# power.net
KiCad netlist of a schematic drawn in Altium Designer
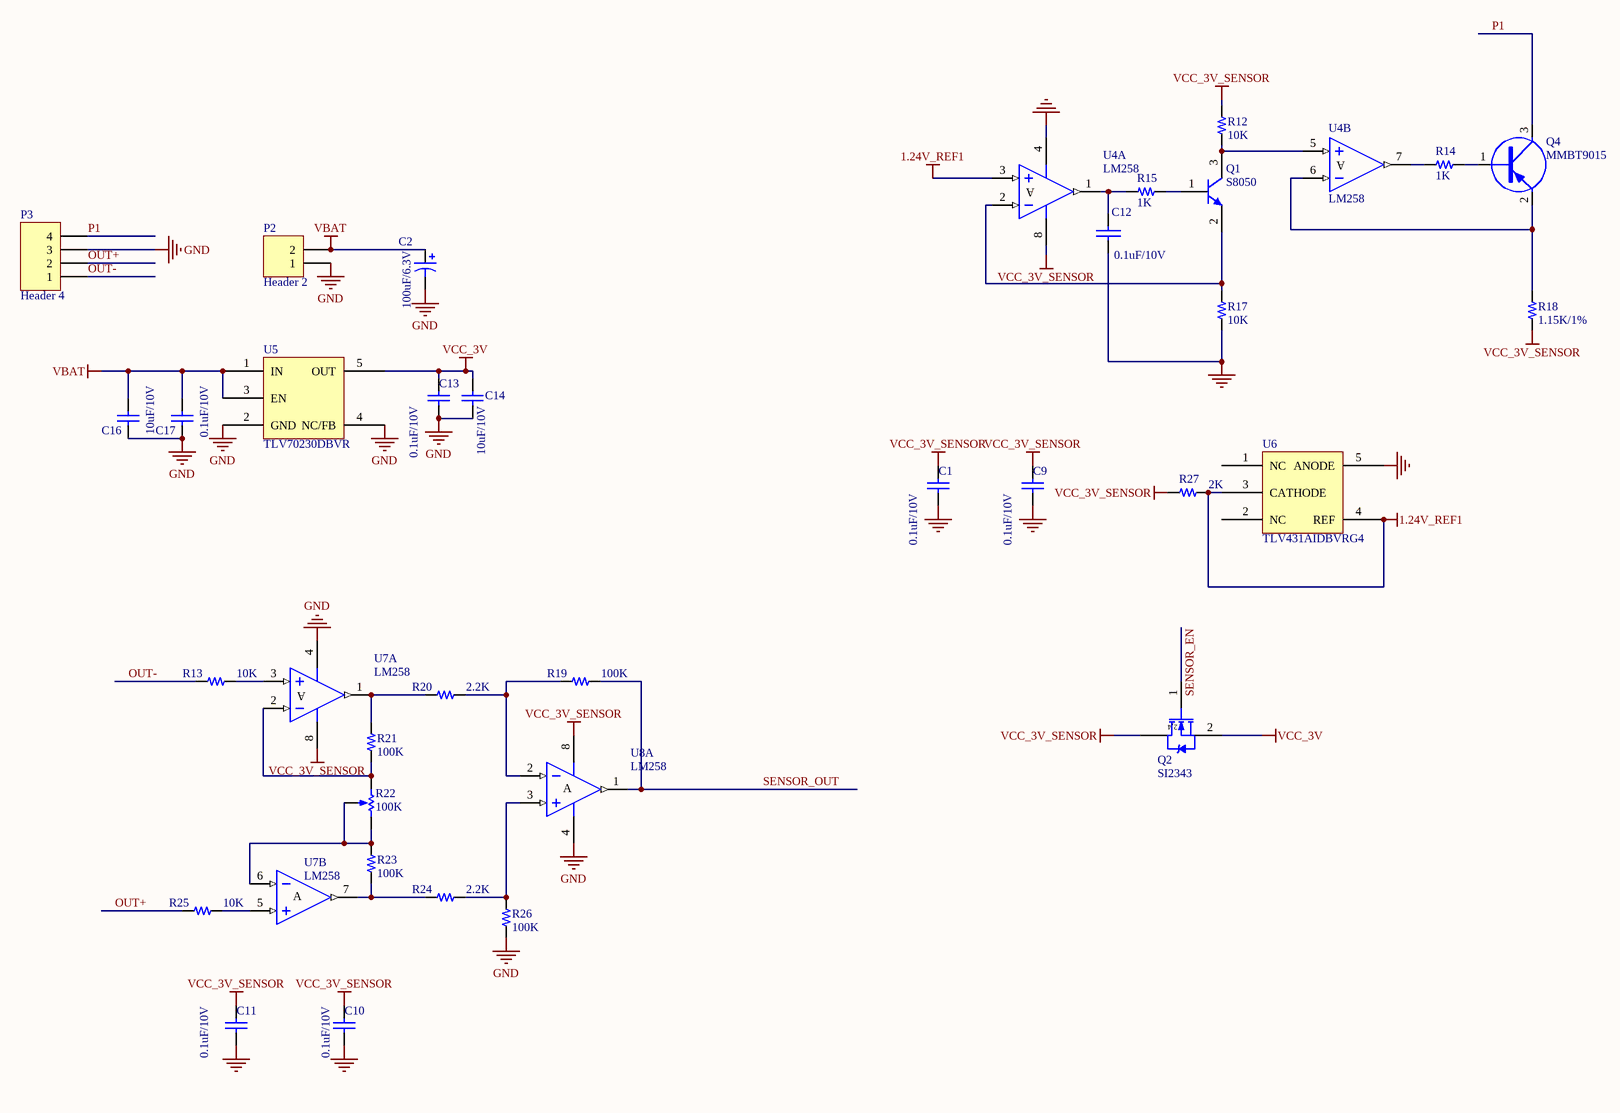
[diagram p0: power.SchDoc]

(export (version "E")
  (design (tool "Eeschema 10.0.6"))
  (components
    (comp (ref "C1")
      (value "0.1uF/10V")
      (footprint "0603C")
      (description "Capacitor")
      (fields (field (name "PUBLISHER") "Altium Limited"))
      (libsource (lib "Miscellaneous Devices") (part "Cap"))
    )
    (comp (ref "C2")
      (value "100uF/6.3V")
      (footprint "7343")
      (description "Polarized Capacitor (Radial)")
      (fields (field (name "PUBLISHER") "Altium Limited"))
      (libsource (lib "Miscellaneous Devices") (part "Cap Pol1"))
    )
    (comp (ref "C9")
      (value "0.1uF/10V")
      (footprint "0603C")
      (description "Capacitor")
      (fields (field (name "PUBLISHER") "Altium Limited"))
      (libsource (lib "Miscellaneous Devices") (part "Cap"))
    )
    (comp (ref "C10")
      (value "0.1uF/10V")
      (footprint "0603C")
      (description "Capacitor")
      (fields (field (name "PUBLISHER") "Altium Limited"))
      (libsource (lib "Miscellaneous Devices") (part "Cap"))
    )
    (comp (ref "C11")
      (value "0.1uF/10V")
      (footprint "0603C")
      (description "Capacitor")
      (fields (field (name "PUBLISHER") "Altium Limited"))
      (libsource (lib "Miscellaneous Devices") (part "Cap"))
    )
    (comp (ref "C12")
      (value "0.1uF/10V")
      (footprint "0603C")
      (description "Capacitor")
      (libsource (lib "*") (part "CAP"))
    )
    (comp (ref "C13")
      (value "0.1uF/10V")
      (footprint "0603C")
      (description "Capacitor")
      (fields (field (name "PUBLISHER") "Altium Limited"))
      (libsource (lib "Miscellaneous Devices") (part "Cap"))
    )
    (comp (ref "C14")
      (value "10uF/10V")
      (footprint "0603C")
      (description "Capacitor")
      (fields (field (name "PUBLISHER") "Altium Limited"))
      (libsource (lib "Miscellaneous Devices") (part "Cap"))
    )
    (comp (ref "C16")
      (value "10uF/10V")
      (footprint "0603C")
      (description "Capacitor")
      (fields (field (name "PUBLISHER") "Altium Limited"))
      (libsource (lib "Miscellaneous Devices") (part "Cap"))
    )
    (comp (ref "C17")
      (value "0.1uF/10V")
      (footprint "0603C")
      (description "Capacitor")
      (fields (field (name "PUBLISHER") "Altium Limited"))
      (libsource (lib "Miscellaneous Devices") (part "Cap"))
    )
    (comp (ref "P2")
      (value "Header 2")
      (footprint "2X2.54MM")
      (description "Header, 2-Pin")
      (fields (field (name "PUBLISHER") "Altium Limited"))
      (libsource (lib "Miscellaneous Connectors") (part "Header 2"))
    )
    (comp (ref "P3")
      (value "Header 4")
      (footprint "HDR1X4")
      (description "Header, 4-Pin")
      (fields (field (name "PUBLISHER") "Altium Limited"))
      (libsource (lib "Miscellaneous Connectors") (part "Header 4"))
    )
    (comp (ref "Q1") (value "S8050") (footprint "SOT23-3") (libsource (lib "Schlib1") (part "NPN")))
    (comp (ref "Q2")
      (value "SI2343")
      (footprint "SOT23-3")
      (description "BUK92150-55A")
      (fields (field (name "PUBLISHER") "Altium Limited"))
      (libsource (lib "Schlib1") (part "BUK92150-55A"))
    )
    (comp (ref "Q4") (value "MMBT9015") (footprint "SOT23-3") (libsource (lib "Schlib1") (part "PNP")))
    (comp (ref "R12")
      (value "10K")
      (footprint "0603R")
      (description "R")
      (libsource (lib "JRJ_1") (part "R"))
    )
    (comp (ref "R13")
      (value "10K")
      (footprint "0603R")
      (description "R")
      (libsource (lib "JRJ_1") (part "R"))
    )
    (comp (ref "R14") (value "1K") (footprint "0603R") (description "R") (libsource (lib "JRJ_1") (part "R")))
    (comp (ref "R15") (value "1K") (footprint "0603R") (description "R") (libsource (lib "JRJ_1") (part "R")))
    (comp (ref "R17")
      (value "10K")
      (footprint "0603R")
      (description "R")
      (libsource (lib "JRJ_1") (part "R"))
    )
    (comp (ref "R18")
      (value "1.15K/1%")
      (footprint "0603R")
      (description "R")
      (libsource (lib "JRJ_1") (part "R"))
    )
    (comp (ref "R19")
      (value "100K")
      (footprint "0603R")
      (description "R")
      (libsource (lib "JRJ_1") (part "R"))
    )
    (comp (ref "R20")
      (value "2.2K")
      (footprint "0603R")
      (description "R")
      (libsource (lib "JRJ_1") (part "R"))
    )
    (comp (ref "R21")
      (value "100K")
      (footprint "0603R")
      (description "R")
      (libsource (lib "JRJ_1") (part "R"))
    )
    (comp (ref "R22")
      (value "100K")
      (footprint "HDR1X3")
      (description "Potentiometer")
      (fields (field (name "PUBLISHER") "Altium Limited"))
      (libsource (lib "Miscellaneous Devices") (part "RPot"))
    )
    (comp (ref "R23")
      (value "100K")
      (footprint "0603R")
      (description "R")
      (libsource (lib "JRJ_1") (part "R"))
    )
    (comp (ref "R24")
      (value "2.2K")
      (footprint "0603R")
      (description "R")
      (libsource (lib "JRJ_1") (part "R"))
    )
    (comp (ref "R25")
      (value "10K")
      (footprint "0603R")
      (description "R")
      (libsource (lib "JRJ_1") (part "R"))
    )
    (comp (ref "R26")
      (value "100K")
      (footprint "0603R")
      (description "R")
      (libsource (lib "JRJ_1") (part "R"))
    )
    (comp (ref "R27") (value "2K") (footprint "0603R") (description "R") (libsource (lib "JRJ_1") (part "R")))
    (comp (ref "U4") (value "LM258") (footprint "so-8") (libsource (lib "Schlib_20110825") (part "LM258")))
    (comp (ref "U5")
      (value "TLV70230DBVR")
      (footprint "SOT23-5(DBV)")
      (libsource (lib "Schlib_20110825") (part "TLV70230DBVR"))
    )
    (comp (ref "U6")
      (value "TLV431AIDBVRG4")
      (footprint "SOT23-5(DBV)")
      (libsource (lib "Schlib_20110825") (part "TPS76318"))
    )
    (comp (ref "U7") (value "LM258") (footprint "so-8") (libsource (lib "Schlib_20110825") (part "LM258")))
    (comp (ref "U8") (value "LM258") (footprint "so-8") (libsource (lib "Schlib_20110825") (part "LM258")))
  )
  (nets
    (net (code "1") (name "/OUT+") (class "Default")
      (node (ref "P3") (pin "2") (pinfunction "2_2") (pintype "passive"))
      (node (ref "R25") (pin "1") (pintype "passive"))
    )
    (net (code "2") (name "/OUT-") (class "Default")
      (node (ref "P3") (pin "1") (pinfunction "1_1") (pintype "passive"))
      (node (ref "R13") (pin "1") (pintype "passive"))
    )
    (net (code "3") (name "/P1") (class "Default")
      (node (ref "P3") (pin "4") (pinfunction "4_4") (pintype "passive"))
      (node (ref "Q4") (pin "3") (pinfunction "C_3") (pintype "passive"))
    )
    (net (code "4") (name "/SENSOR_EN") (class "Default")
      (node (ref "Q2") (pin "1") (pinfunction "G_1") (pintype "passive"))
    )
    (net (code "5") (name "/SENSOR_OUT") (class "Default")
      (node (ref "R19") (pin "2") (pintype "passive"))
      (node (ref "U8") (pin "1") (pinfunction "OUT_1") (pintype "output"))
    )
    (net (code "6") (name "1.24V_REF1") (class "Default")
      (node (ref "R27") (pin "2") (pintype "passive"))
      (node (ref "U4") (pin "3") (pinfunction "IN+_3") (pintype "input"))
      (node (ref "U6") (pin "3") (pinfunction "CATHODE_3") (pintype "passive"))
      (node (ref "U6") (pin "4") (pinfunction "REF_4") (pintype "passive"))
    )
    (net (code "7") (name "GND") (class "Default")
      (node (ref "C1") (pin "2") (pinfunction "2_2") (pintype "passive"))
      (node (ref "C10") (pin "2") (pinfunction "2_2") (pintype "passive"))
      (node (ref "C11") (pin "2") (pinfunction "2_2") (pintype "passive"))
      (node (ref "C12") (pin "2") (pinfunction "2_2") (pintype "passive"))
      (node (ref "C13") (pin "2") (pinfunction "2_2") (pintype "passive"))
      (node (ref "C14") (pin "1") (pinfunction "1_1") (pintype "passive"))
      (node (ref "C16") (pin "1") (pinfunction "1_1") (pintype "passive"))
      (node (ref "C17") (pin "2") (pinfunction "2_2") (pintype "passive"))
      (node (ref "C2") (pin "2") (pinfunction "2_2") (pintype "passive"))
      (node (ref "C9") (pin "2") (pinfunction "2_2") (pintype "passive"))
      (node (ref "P2") (pin "1") (pinfunction "1_1") (pintype "passive"))
      (node (ref "P3") (pin "3") (pinfunction "3_3") (pintype "passive"))
      (node (ref "R17") (pin "1") (pintype "passive"))
      (node (ref "R26") (pin "1") (pintype "passive"))
      (node (ref "U4") (pin "4") (pinfunction "V-_4") (pintype "power_in"))
      (node (ref "U5") (pin "2") (pinfunction "GND_2") (pintype "passive"))
      (node (ref "U5") (pin "4") (pinfunction "NC/FB_4") (pintype "passive"))
      (node (ref "U6") (pin "5") (pinfunction "ANODE_5") (pintype "passive"))
      (node (ref "U7") (pin "4") (pinfunction "V-_4") (pintype "power_in"))
      (node (ref "U8") (pin "4") (pinfunction "V-_4") (pintype "power_in"))
    )
    (net (code "8") (name "Net-(Q1-B)") (class "Default")
      (node (ref "Q1") (pin "1") (pinfunction "B_1") (pintype "passive"))
      (node (ref "R15") (pin "2") (pintype "passive"))
    )
    (net (code "9") (name "Net-(Q1-C)") (class "Default")
      (node (ref "Q1") (pin "3") (pinfunction "C_3") (pintype "passive"))
      (node (ref "R12") (pin "1") (pintype "passive"))
      (node (ref "U4") (pin "5") (pinfunction "IN+_5") (pintype "input"))
    )
    (net (code "10") (name "Net-(Q1-E)") (class "Default")
      (node (ref "Q1") (pin "2") (pinfunction "E_2") (pintype "passive"))
      (node (ref "R17") (pin "2") (pintype "passive"))
      (node (ref "U4") (pin "2") (pinfunction "IN-_2") (pintype "input"))
    )
    (net (code "11") (name "Net-(Q4-B)") (class "Default")
      (node (ref "Q4") (pin "1") (pinfunction "B_1") (pintype "passive"))
      (node (ref "R14") (pin "2") (pintype "passive"))
    )
    (net (code "12") (name "Net-(Q4-E)") (class "Default")
      (node (ref "Q4") (pin "2") (pinfunction "E_2") (pintype "passive"))
      (node (ref "R18") (pin "2") (pintype "passive"))
      (node (ref "U4") (pin "6") (pinfunction "IN-_6") (pintype "input"))
    )
    (net (code "13") (name "Net-(R22-BOT)") (class "Default")
      (node (ref "R22") (pin "2") (pinfunction "BOT_2") (pintype "passive"))
      (node (ref "R22") (pin "3") (pinfunction "TAP_3") (pintype "passive"))
      (node (ref "R23") (pin "2") (pintype "passive"))
      (node (ref "U7") (pin "6") (pinfunction "IN-_6") (pintype "input"))
    )
    (net (code "14") (name "Net-(R22-TOP)") (class "Default")
      (node (ref "R21") (pin "1") (pintype "passive"))
      (node (ref "R22") (pin "1") (pinfunction "TOP_1") (pintype "passive"))
      (node (ref "U7") (pin "2") (pinfunction "IN-_2") (pintype "input"))
    )
    (net (code "15") (name "Net-(U4A-OUT)") (class "Default")
      (node (ref "C12") (pin "1") (pinfunction "1_1") (pintype "passive"))
      (node (ref "R15") (pin "1") (pintype "passive"))
      (node (ref "U4") (pin "1") (pinfunction "OUT_1") (pintype "output"))
    )
    (net (code "16") (name "Net-(U4B-OUT)") (class "Default")
      (node (ref "R14") (pin "1") (pintype "passive"))
      (node (ref "U4") (pin "7") (pinfunction "OUT_7") (pintype "output"))
    )
    (net (code "17") (name "Net-(U7A-IN+)") (class "Default")
      (node (ref "R13") (pin "2") (pintype "passive"))
      (node (ref "U7") (pin "3") (pinfunction "IN+_3") (pintype "input"))
    )
    (net (code "18") (name "Net-(U7A-OUT)") (class "Default")
      (node (ref "R20") (pin "1") (pintype "passive"))
      (node (ref "R21") (pin "2") (pintype "passive"))
      (node (ref "U7") (pin "1") (pinfunction "OUT_1") (pintype "output"))
    )
    (net (code "19") (name "Net-(U7B-IN+)") (class "Default")
      (node (ref "R25") (pin "2") (pintype "passive"))
      (node (ref "U7") (pin "5") (pinfunction "IN+_5") (pintype "input"))
    )
    (net (code "20") (name "Net-(U7B-OUT)") (class "Default")
      (node (ref "R23") (pin "1") (pintype "passive"))
      (node (ref "R24") (pin "1") (pintype "passive"))
      (node (ref "U7") (pin "7") (pinfunction "OUT_7") (pintype "output"))
    )
    (net (code "21") (name "Net-(U8A-IN+)") (class "Default")
      (node (ref "R24") (pin "2") (pintype "passive"))
      (node (ref "R26") (pin "2") (pintype "passive"))
      (node (ref "U8") (pin "3") (pinfunction "IN+_3") (pintype "input"))
    )
    (net (code "22") (name "Net-(U8A-IN-)") (class "Default")
      (node (ref "R19") (pin "1") (pintype "passive"))
      (node (ref "R20") (pin "2") (pintype "passive"))
      (node (ref "U8") (pin "2") (pinfunction "IN-_2") (pintype "input"))
    )
    (net (code "23") (name "VBAT") (class "Default")
      (node (ref "C16") (pin "2") (pinfunction "2_2") (pintype "passive"))
      (node (ref "C17") (pin "1") (pinfunction "1_1") (pintype "passive"))
      (node (ref "C2") (pin "1") (pinfunction "1_1") (pintype "passive"))
      (node (ref "P2") (pin "2") (pinfunction "2_2") (pintype "passive"))
      (node (ref "U5") (pin "1") (pinfunction "IN_1") (pintype "passive"))
      (node (ref "U5") (pin "3") (pinfunction "EN_3") (pintype "passive"))
    )
    (net (code "24") (name "VCC_3V") (class "Default")
      (node (ref "C13") (pin "1") (pinfunction "1_1") (pintype "passive"))
      (node (ref "C14") (pin "2") (pinfunction "2_2") (pintype "passive"))
      (node (ref "Q2") (pin "2") (pinfunction "S_2") (pintype "passive"))
      (node (ref "U5") (pin "5") (pinfunction "OUT_5") (pintype "passive"))
    )
    (net (code "25") (name "VCC_3V_SENSOR") (class "Default")
      (node (ref "C1") (pin "1") (pinfunction "1_1") (pintype "passive"))
      (node (ref "C10") (pin "1") (pinfunction "1_1") (pintype "passive"))
      (node (ref "C11") (pin "1") (pinfunction "1_1") (pintype "passive"))
      (node (ref "C9") (pin "1") (pinfunction "1_1") (pintype "passive"))
      (node (ref "Q2") (pin "3") (pinfunction "D_3") (pintype "passive"))
      (node (ref "R12") (pin "2") (pintype "passive"))
      (node (ref "R18") (pin "1") (pintype "passive"))
      (node (ref "R27") (pin "1") (pintype "passive"))
      (node (ref "U4") (pin "8") (pinfunction "V+_8") (pintype "power_in"))
      (node (ref "U7") (pin "8") (pinfunction "V+_8") (pintype "power_in"))
      (node (ref "U8") (pin "8") (pinfunction "V+_8") (pintype "power_in"))
    )
    (net (code "26") (name "unconnected-(U6-NC-Pad1)") (class "Default")
      (node (ref "U6") (pin "1") (pinfunction "NC_1") (pintype "passive"))
    )
    (net (code "27") (name "unconnected-(U6-NC-Pad2)") (class "Default")
      (node (ref "U6") (pin "2") (pinfunction "NC_2") (pintype "passive"))
    )
  )
)
